# DCDCConverter.net
KiCad netlist of a schematic drawn in EAGLE
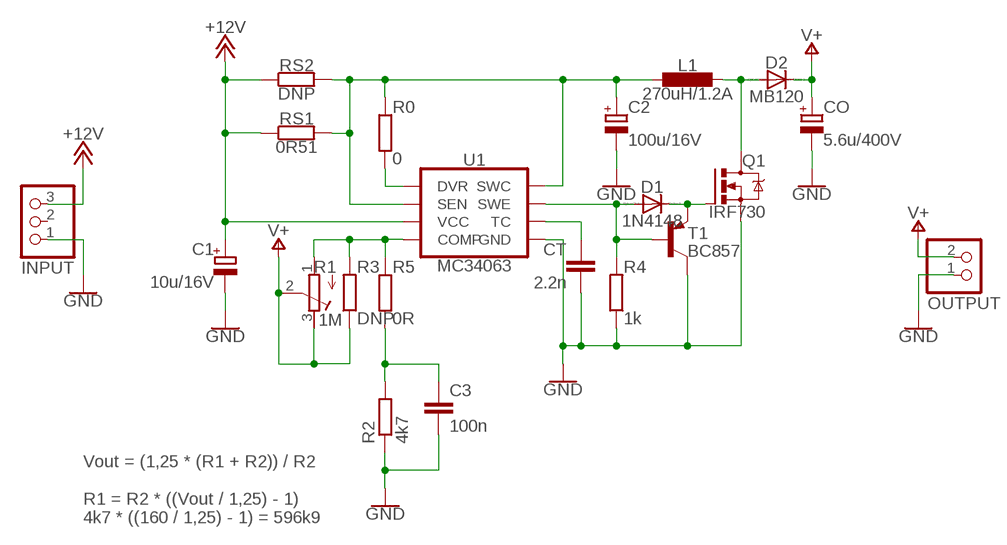
[diagram p0: schematic, sheet 1]

(export (version "E")
  (design (tool "Eeschema 10.0.6"))
  (components
    (comp (ref "C1")
      (value "10u/16V")
      (footprint "eagle-import:140CLH-0810")
      (libsource (lib "eagle-import") (part "CPOL-EU140CLH-0810"))
    )
    (comp (ref "C2")
      (value "100u/16V")
      (footprint "eagle-import:140CLH-0810")
      (libsource (lib "eagle-import") (part "CPOL-EU140CLH-0810"))
    )
    (comp (ref "C3")
      (value "100n")
      (footprint "eagle-import:C0603K")
      (libsource (lib "eagle-import") (part "C-EUC0603K"))
    )
    (comp (ref "CO")
      (value "5.6u/400V")
      (footprint "eagle-import:153CLV-1010")
      (libsource (lib "eagle-import") (part "CPOL-EU153CLV-1010"))
    )
    (comp (ref "CT")
      (value "2.2n")
      (footprint "eagle-import:C0603K")
      (libsource (lib "eagle-import") (part "C-EUC0603K"))
    )
    (comp (ref "D1")
      (value "1N4148")
      (footprint "eagle-import:SOD323-W")
      (libsource (lib "eagle-import") (part "DIODE-SOD323-W"))
    )
    (comp (ref "D2")
      (value "MB120")
      (footprint "eagle-import:DO214AA")
      (libsource (lib "eagle-import") (part "DIODE-DO214AA"))
    )
    (comp (ref "INPUT")
      (value "PINHD-1X3")
      (footprint "eagle-import:1X03")
      (libsource (lib "eagle-import") (part "PINHD-1X3"))
    )
    (comp (ref "L1")
      (value "270uH/1.2A")
      (footprint "eagle-import:TC-PIS4728")
      (libsource (lib "eagle-import") (part "TC-PIS4728"))
    )
    (comp (ref "OUTPUT")
      (value "PINHD-1X2")
      (footprint "eagle-import:1X02")
      (libsource (lib "eagle-import") (part "PINHD-1X2"))
    )
    (comp (ref "Q1")
      (value "IRF730")
      (footprint "eagle-import:TO220BV")
      (libsource (lib "eagle-import") (part "IRF740"))
    )
    (comp (ref "R0")
      (value "0")
      (footprint "eagle-import:R0603")
      (libsource (lib "eagle-import") (part "R-EU_R0603"))
    )
    (comp (ref "R1")
      (value "1M")
      (footprint "eagle-import:RTRIM64W")
      (libsource (lib "eagle-import") (part "R-TRIMM64W"))
    )
    (comp (ref "R2")
      (value "4k7")
      (footprint "eagle-import:R0603")
      (libsource (lib "eagle-import") (part "R-EU_R0603"))
    )
    (comp (ref "R3")
      (value "DNP")
      (footprint "eagle-import:R0603")
      (libsource (lib "eagle-import") (part "R-EU_R0603"))
    )
    (comp (ref "R4")
      (value "1k")
      (footprint "eagle-import:R0603")
      (libsource (lib "eagle-import") (part "R-EU_R0603"))
    )
    (comp (ref "R5")
      (value "0R")
      (footprint "eagle-import:R0603")
      (libsource (lib "eagle-import") (part "R-EU_R0603"))
    )
    (comp (ref "RS1")
      (value "0R51")
      (footprint "eagle-import:R2512")
      (libsource (lib "eagle-import") (part "R-EU_R2512"))
    )
    (comp (ref "RS2")
      (value "DNP")
      (footprint "eagle-import:R2512")
      (libsource (lib "eagle-import") (part "R-EU_R2512"))
    )
    (comp (ref "T1")
      (value "BC857")
      (footprint "eagle-import:SOT23-BEC")
      (libsource (lib "eagle-import") (part "-PNP-SOT23-BECBC857A"))
    )
    (comp (ref "U1")
      (value "MC34063")
      (footprint "eagle-import:SOIC127P600X175-8")
      (libsource (lib "eagle-import") (part "MC34063"))
    )
  )
  (nets
    (net (code "1") (name "+12V") (class "Default")
      (node (ref "C1") (pin "+") (pinfunction "+_+") (pintype "passive"))
      (node (ref "INPUT") (pin "3") (pinfunction "3_3") (pintype "passive"))
      (node (ref "RS1") (pin "1") (pinfunction "1_1") (pintype "passive"))
      (node (ref "RS2") (pin "1") (pinfunction "1_1") (pintype "passive"))
      (node (ref "U1") (pin "6") (pinfunction "VCC_6") (pintype "bidirectional"))
    )
    (net (code "2") (name "GND") (class "Default")
      (node (ref "C1") (pin "-") (pinfunction "-_-") (pintype "passive"))
      (node (ref "C2") (pin "-") (pinfunction "-_-") (pintype "passive"))
      (node (ref "C3") (pin "2") (pinfunction "2_2") (pintype "passive"))
      (node (ref "CO") (pin "-") (pinfunction "-_-") (pintype "passive"))
      (node (ref "CT") (pin "1") (pinfunction "1_1") (pintype "passive"))
      (node (ref "INPUT") (pin "1") (pinfunction "1_1") (pintype "passive"))
      (node (ref "OUTPUT") (pin "1") (pinfunction "1_1") (pintype "passive"))
      (node (ref "Q1") (pin "S") (pinfunction "S_S") (pintype "passive"))
      (node (ref "R2") (pin "1") (pinfunction "1_1") (pintype "passive"))
      (node (ref "R4") (pin "1") (pinfunction "1_1") (pintype "passive"))
      (node (ref "T1") (pin "C") (pinfunction "C_C") (pintype "passive"))
      (node (ref "U1") (pin "4") (pinfunction "GND_4") (pintype "bidirectional"))
    )
    (net (code "3") (name "Net-(C3-Pad1)") (class "Default")
      (node (ref "C3") (pin "1") (pinfunction "1_1") (pintype "passive"))
      (node (ref "R2") (pin "2") (pinfunction "2_2") (pintype "passive"))
      (node (ref "R5") (pin "2") (pinfunction "2_2") (pintype "passive"))
    )
    (net (code "4") (name "Net-(D1-PadC)") (class "Default")
      (node (ref "D1") (pin "C") (pinfunction "C_C") (pintype "passive"))
      (node (ref "Q1") (pin "G") (pinfunction "G_G") (pintype "passive"))
      (node (ref "T1") (pin "E") (pinfunction "E_E") (pintype "passive"))
    )
    (net (code "5") (name "Net-(L1-1)") (class "Default")
      (node (ref "D2") (pin "A") (pinfunction "A_A") (pintype "passive"))
      (node (ref "L1") (pin "P$1") (pinfunction "1_P$1") (pintype "passive"))
      (node (ref "Q1") (pin "D") (pinfunction "D_D") (pintype "passive"))
    )
    (net (code "6") (name "Net-(L1-2)") (class "Default")
      (node (ref "C2") (pin "+") (pinfunction "+_+") (pintype "passive"))
      (node (ref "L1") (pin "P$2") (pinfunction "2_P$2") (pintype "passive"))
      (node (ref "R0") (pin "1") (pinfunction "1_1") (pintype "passive"))
      (node (ref "RS1") (pin "2") (pinfunction "2_2") (pintype "passive"))
      (node (ref "RS2") (pin "2") (pinfunction "2_2") (pintype "passive"))
      (node (ref "U1") (pin "1") (pinfunction "SWC_1") (pintype "bidirectional"))
      (node (ref "U1") (pin "7") (pinfunction "SEN_7") (pintype "bidirectional"))
    )
    (net (code "7") (name "Net-(R1-A)") (class "Default")
      (node (ref "R1") (pin "1") (pinfunction "A_1") (pintype "passive"))
      (node (ref "R3") (pin "2") (pinfunction "2_2") (pintype "passive"))
      (node (ref "R5") (pin "1") (pinfunction "1_1") (pintype "passive"))
      (node (ref "U1") (pin "5") (pinfunction "COMP_5") (pintype "bidirectional"))
    )
    (net (code "8") (name "Net-(U1-DVR)") (class "Default")
      (node (ref "R0") (pin "2") (pinfunction "2_2") (pintype "passive"))
      (node (ref "U1") (pin "8") (pinfunction "DVR_8") (pintype "bidirectional"))
    )
    (net (code "9") (name "Net-(U1-SWE)") (class "Default")
      (node (ref "D1") (pin "A") (pinfunction "A_A") (pintype "passive"))
      (node (ref "R4") (pin "2") (pinfunction "2_2") (pintype "passive"))
      (node (ref "T1") (pin "B") (pinfunction "B_B") (pintype "passive"))
      (node (ref "U1") (pin "2") (pinfunction "SWE_2") (pintype "bidirectional"))
    )
    (net (code "10") (name "Net-(U1-TC)") (class "Default")
      (node (ref "CT") (pin "2") (pinfunction "2_2") (pintype "passive"))
      (node (ref "U1") (pin "3") (pinfunction "TC_3") (pintype "bidirectional"))
    )
    (net (code "11") (name "V+") (class "Default")
      (node (ref "CO") (pin "+") (pinfunction "+_+") (pintype "passive"))
      (node (ref "D2") (pin "C") (pinfunction "C_C") (pintype "passive"))
      (node (ref "OUTPUT") (pin "2") (pinfunction "2_2") (pintype "passive"))
      (node (ref "R1") (pin "2") (pinfunction "S_2") (pintype "passive"))
      (node (ref "R1") (pin "3") (pinfunction "E_3") (pintype "passive"))
      (node (ref "R3") (pin "1") (pinfunction "1_1") (pintype "passive"))
    )
    (net (code "12") (name "unconnected-(INPUT-Pad2)") (class "Default")
      (node (ref "INPUT") (pin "2") (pinfunction "2_2") (pintype "passive"))
    )
  )
)
